# activity_monitor_v1_3.net
KiCad netlist of a schematic drawn in EAGLE
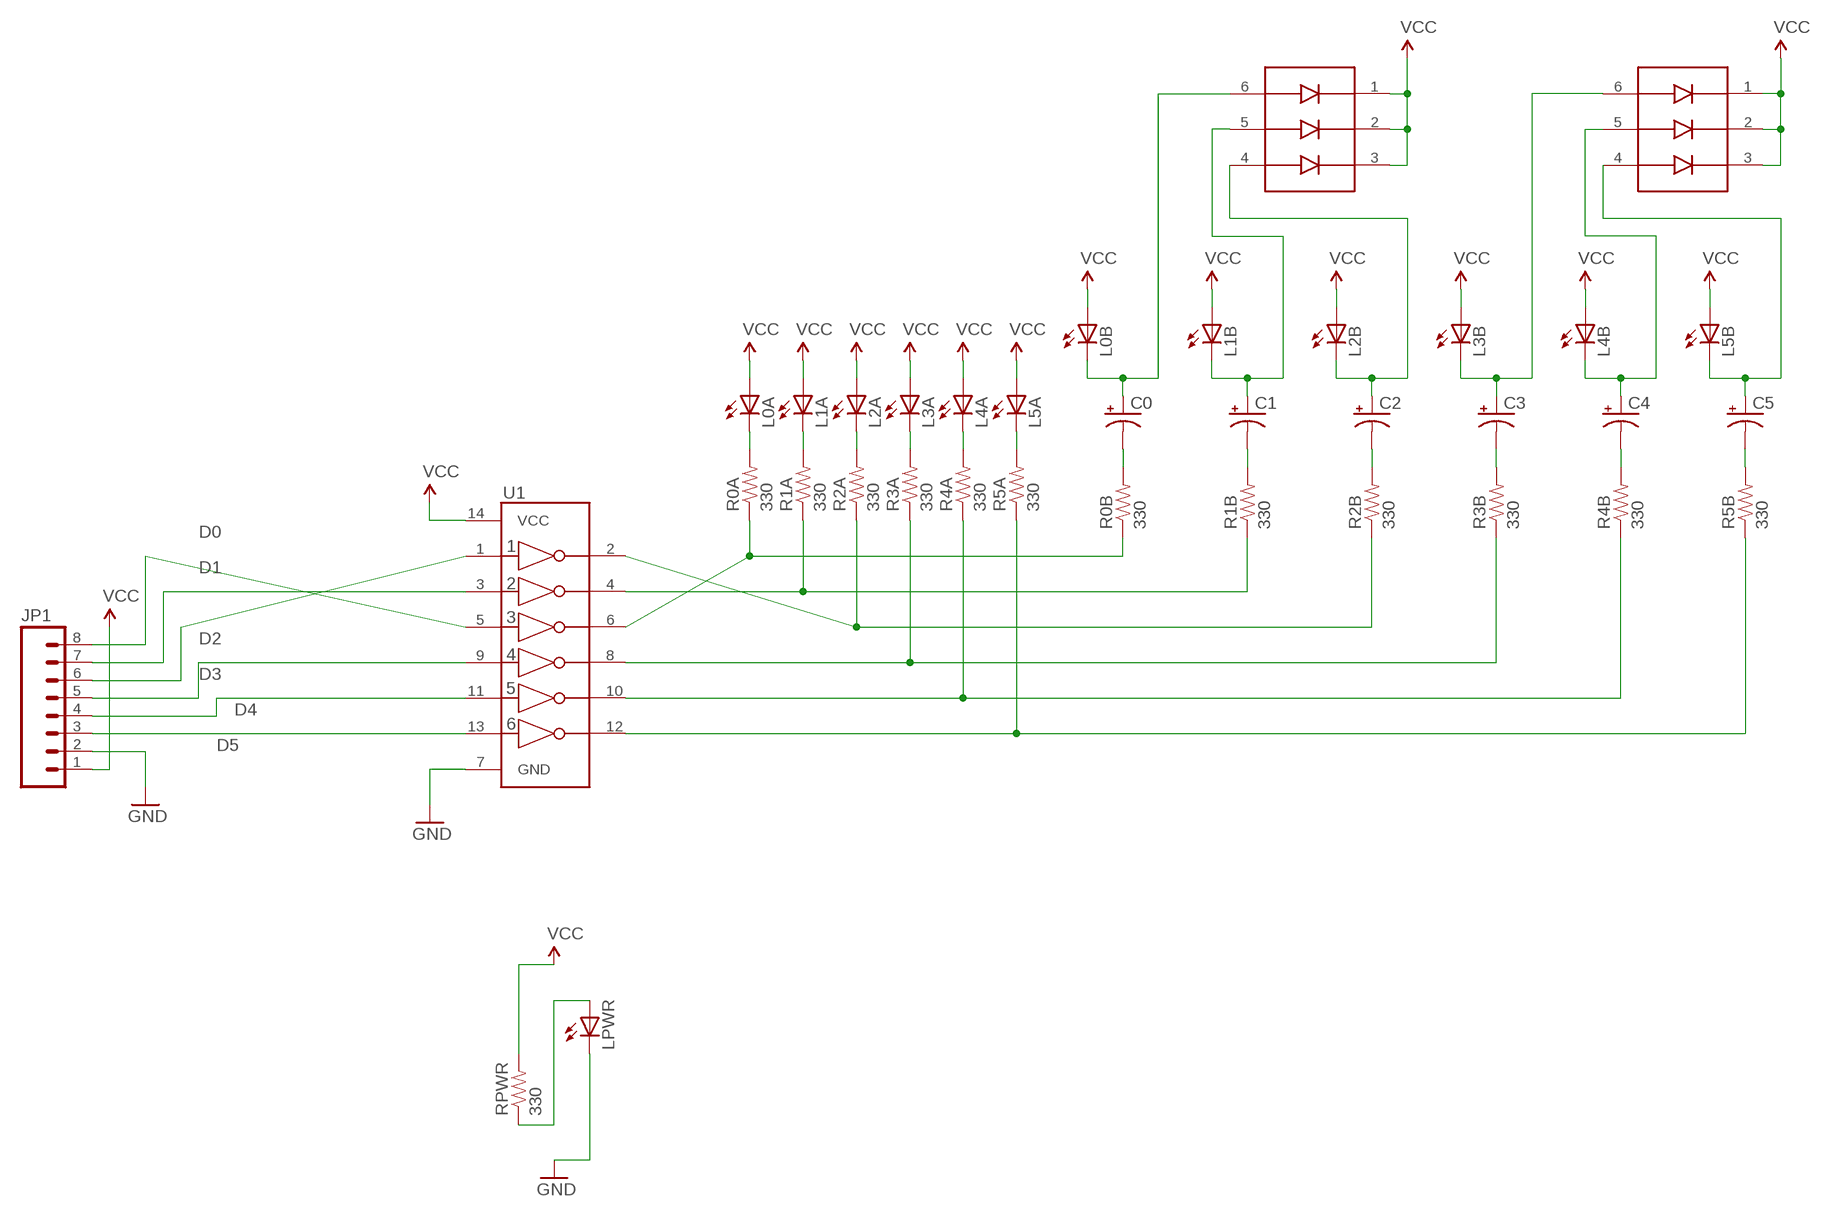
[diagram p0: schematic, sheet 1]

(export (version "E")
  (design (tool "Eeschema 10.0.6"))
  (components
    (comp (ref "C0")
      (value "10UF-TANT")
      (footprint "eagle-import:EIA3216")
      (libsource (lib "eagle-import") (part "10UF-TANT"))
    )
    (comp (ref "C1")
      (value "10UF-TANT")
      (footprint "eagle-import:EIA3216")
      (libsource (lib "eagle-import") (part "10UF-TANT"))
    )
    (comp (ref "C2")
      (value "10UF-TANT")
      (footprint "eagle-import:EIA3216")
      (libsource (lib "eagle-import") (part "10UF-TANT"))
    )
    (comp (ref "C3")
      (value "10UF-TANT")
      (footprint "eagle-import:EIA3216")
      (libsource (lib "eagle-import") (part "10UF-TANT"))
    )
    (comp (ref "C4")
      (value "10UF-TANT")
      (footprint "eagle-import:EIA3216")
      (libsource (lib "eagle-import") (part "10UF-TANT"))
    )
    (comp (ref "C5")
      (value "10UF-TANT")
      (footprint "eagle-import:EIA3216")
      (libsource (lib "eagle-import") (part "10UF-TANT"))
    )
    (comp (ref "JP1")
      (value "M081X08")
      (footprint "eagle-import:1X08")
      (libsource (lib "eagle-import") (part "M081X08"))
    )
    (comp (ref "L0A")
      (value "LED0603")
      (footprint "eagle-import:0603_LED")
      (libsource (lib "eagle-import") (part "LED0603"))
    )
    (comp (ref "L0B")
      (value "LED0603")
      (footprint "eagle-import:0603_LED")
      (libsource (lib "eagle-import") (part "LED0603"))
    )
    (comp (ref "L1A")
      (value "LED0603")
      (footprint "eagle-import:0603_LED")
      (libsource (lib "eagle-import") (part "LED0603"))
    )
    (comp (ref "L1B")
      (value "LED0603")
      (footprint "eagle-import:0603_LED")
      (libsource (lib "eagle-import") (part "LED0603"))
    )
    (comp (ref "L2A")
      (value "LED0603")
      (footprint "eagle-import:0603_LED")
      (libsource (lib "eagle-import") (part "LED0603"))
    )
    (comp (ref "L2B")
      (value "LED0603")
      (footprint "eagle-import:0603_LED")
      (libsource (lib "eagle-import") (part "LED0603"))
    )
    (comp (ref "L3A")
      (value "LED0603")
      (footprint "eagle-import:0603_LED")
      (libsource (lib "eagle-import") (part "LED0603"))
    )
    (comp (ref "L3B")
      (value "LED0603")
      (footprint "eagle-import:0603_LED")
      (libsource (lib "eagle-import") (part "LED0603"))
    )
    (comp (ref "L4A")
      (value "LED0603")
      (footprint "eagle-import:0603_LED")
      (libsource (lib "eagle-import") (part "LED0603"))
    )
    (comp (ref "L4B")
      (value "LED0603")
      (footprint "eagle-import:0603_LED")
      (libsource (lib "eagle-import") (part "LED0603"))
    )
    (comp (ref "L5A")
      (value "LED0603")
      (footprint "eagle-import:0603_LED")
      (libsource (lib "eagle-import") (part "LED0603"))
    )
    (comp (ref "L5B")
      (value "LED0603")
      (footprint "eagle-import:0603_LED")
      (libsource (lib "eagle-import") (part "LED0603"))
    )
    (comp (ref "LPWR")
      (value "LED0603")
      (footprint "eagle-import:0603_LED")
      (libsource (lib "eagle-import") (part "LED0603"))
    )
    (comp (ref "R0A")
      (value "330")
      (footprint "eagle-import:0603-RES")
      (libsource (lib "eagle-import") (part "RESISTOR0603"))
    )
    (comp (ref "R0B")
      (value "330")
      (footprint "eagle-import:0603-RES")
      (libsource (lib "eagle-import") (part "RESISTOR0603"))
    )
    (comp (ref "R1A")
      (value "330")
      (footprint "eagle-import:0603-RES")
      (libsource (lib "eagle-import") (part "RESISTOR0603"))
    )
    (comp (ref "R1B")
      (value "330")
      (footprint "eagle-import:0603-RES")
      (libsource (lib "eagle-import") (part "RESISTOR0603"))
    )
    (comp (ref "R2A")
      (value "330")
      (footprint "eagle-import:0603-RES")
      (libsource (lib "eagle-import") (part "RESISTOR0603"))
    )
    (comp (ref "R2B")
      (value "330")
      (footprint "eagle-import:0603-RES")
      (libsource (lib "eagle-import") (part "RESISTOR0603"))
    )
    (comp (ref "R3A")
      (value "330")
      (footprint "eagle-import:0603-RES")
      (libsource (lib "eagle-import") (part "RESISTOR0603"))
    )
    (comp (ref "R3B")
      (value "330")
      (footprint "eagle-import:0603-RES")
      (libsource (lib "eagle-import") (part "RESISTOR0603"))
    )
    (comp (ref "R4A")
      (value "330")
      (footprint "eagle-import:0603-RES")
      (libsource (lib "eagle-import") (part "RESISTOR0603"))
    )
    (comp (ref "R4B")
      (value "330")
      (footprint "eagle-import:0603-RES")
      (libsource (lib "eagle-import") (part "RESISTOR0603"))
    )
    (comp (ref "R5A")
      (value "330")
      (footprint "eagle-import:0603-RES")
      (libsource (lib "eagle-import") (part "RESISTOR0603"))
    )
    (comp (ref "R5B")
      (value "330")
      (footprint "eagle-import:0603-RES")
      (libsource (lib "eagle-import") (part "RESISTOR0603"))
    )
    (comp (ref "RPWR")
      (value "330")
      (footprint "eagle-import:0603-RES")
      (libsource (lib "eagle-import") (part "RESISTOR0603"))
    )
    (comp (ref "U$1")
      (value "SD103ATW-7-F")
      (footprint "eagle-import:SOT363")
      (libsource (lib "eagle-import") (part "SD103ATW-7-F"))
    )
    (comp (ref "U$2")
      (value "SD103ATW-7-F")
      (footprint "eagle-import:SOT363")
      (libsource (lib "eagle-import") (part "SD103ATW-7-F"))
    )
    (comp (ref "U1")
      (value "74HC04_HEX_INVERTERTSSOP14")
      (footprint "eagle-import:TSSOP14")
      (libsource (lib "eagle-import") (part "74HC04_HEX_INVERTERTSSOP14"))
    )
  )
  (nets
    (net (code "1") (name "/D0") (class "Default")
      (node (ref "JP1") (pin "8") (pinfunction "8_8") (pintype "passive"))
      (node (ref "U1") (pin "5") (pinfunction "3A_5") (pintype "input"))
    )
    (net (code "2") (name "/D1") (class "Default")
      (node (ref "JP1") (pin "7") (pinfunction "7_7") (pintype "passive"))
      (node (ref "U1") (pin "3") (pinfunction "2A_3") (pintype "input"))
    )
    (net (code "3") (name "/D2") (class "Default")
      (node (ref "JP1") (pin "6") (pinfunction "6_6") (pintype "passive"))
      (node (ref "U1") (pin "1") (pinfunction "1A_1") (pintype "input"))
    )
    (net (code "4") (name "/D3") (class "Default")
      (node (ref "JP1") (pin "5") (pinfunction "5_5") (pintype "passive"))
      (node (ref "U1") (pin "9") (pinfunction "4A_9") (pintype "input"))
    )
    (net (code "5") (name "/D4") (class "Default")
      (node (ref "JP1") (pin "4") (pinfunction "4_4") (pintype "passive"))
      (node (ref "U1") (pin "11") (pinfunction "5A_11") (pintype "input"))
    )
    (net (code "6") (name "/D5") (class "Default")
      (node (ref "JP1") (pin "3") (pinfunction "3_3") (pintype "passive"))
      (node (ref "U1") (pin "13") (pinfunction "6A_13") (pintype "input"))
    )
    (net (code "7") (name "GND") (class "Default")
      (node (ref "JP1") (pin "2") (pinfunction "2_2") (pintype "passive"))
      (node (ref "LPWR") (pin "C") (pinfunction "C_C") (pintype "passive"))
      (node (ref "U1") (pin "7") (pinfunction "GND_7") (pintype "power_in"))
    )
    (net (code "8") (name "Net-(C0-+)") (class "Default")
      (node (ref "C0") (pin "A") (pinfunction "+_A") (pintype "passive"))
      (node (ref "L0B") (pin "C") (pinfunction "C_C") (pintype "passive"))
      (node (ref "U$1") (pin "6") (pinfunction "I1_6") (pintype "bidirectional"))
    )
    (net (code "9") (name "Net-(C0--)") (class "Default")
      (node (ref "C0") (pin "C") (pinfunction "-_C") (pintype "passive"))
      (node (ref "R0B") (pin "2") (pinfunction "2_2") (pintype "passive"))
    )
    (net (code "10") (name "Net-(C1-+)") (class "Default")
      (node (ref "C1") (pin "A") (pinfunction "+_A") (pintype "passive"))
      (node (ref "L1B") (pin "C") (pinfunction "C_C") (pintype "passive"))
      (node (ref "U$1") (pin "5") (pinfunction "I2_5") (pintype "bidirectional"))
    )
    (net (code "11") (name "Net-(C1--)") (class "Default")
      (node (ref "C1") (pin "C") (pinfunction "-_C") (pintype "passive"))
      (node (ref "R1B") (pin "2") (pinfunction "2_2") (pintype "passive"))
    )
    (net (code "12") (name "Net-(C2-+)") (class "Default")
      (node (ref "C2") (pin "A") (pinfunction "+_A") (pintype "passive"))
      (node (ref "L2B") (pin "C") (pinfunction "C_C") (pintype "passive"))
      (node (ref "U$1") (pin "4") (pinfunction "I3_4") (pintype "bidirectional"))
    )
    (net (code "13") (name "Net-(C2--)") (class "Default")
      (node (ref "C2") (pin "C") (pinfunction "-_C") (pintype "passive"))
      (node (ref "R2B") (pin "2") (pinfunction "2_2") (pintype "passive"))
    )
    (net (code "14") (name "Net-(C3-+)") (class "Default")
      (node (ref "C3") (pin "A") (pinfunction "+_A") (pintype "passive"))
      (node (ref "L3B") (pin "C") (pinfunction "C_C") (pintype "passive"))
      (node (ref "U$2") (pin "6") (pinfunction "I1_6") (pintype "bidirectional"))
    )
    (net (code "15") (name "Net-(C3--)") (class "Default")
      (node (ref "C3") (pin "C") (pinfunction "-_C") (pintype "passive"))
      (node (ref "R3B") (pin "2") (pinfunction "2_2") (pintype "passive"))
    )
    (net (code "16") (name "Net-(C4-+)") (class "Default")
      (node (ref "C4") (pin "A") (pinfunction "+_A") (pintype "passive"))
      (node (ref "L4B") (pin "C") (pinfunction "C_C") (pintype "passive"))
      (node (ref "U$2") (pin "5") (pinfunction "I2_5") (pintype "bidirectional"))
    )
    (net (code "17") (name "Net-(C4--)") (class "Default")
      (node (ref "C4") (pin "C") (pinfunction "-_C") (pintype "passive"))
      (node (ref "R4B") (pin "2") (pinfunction "2_2") (pintype "passive"))
    )
    (net (code "18") (name "Net-(C5-+)") (class "Default")
      (node (ref "C5") (pin "A") (pinfunction "+_A") (pintype "passive"))
      (node (ref "L5B") (pin "C") (pinfunction "C_C") (pintype "passive"))
      (node (ref "U$2") (pin "4") (pinfunction "I3_4") (pintype "bidirectional"))
    )
    (net (code "19") (name "Net-(C5--)") (class "Default")
      (node (ref "C5") (pin "C") (pinfunction "-_C") (pintype "passive"))
      (node (ref "R5B") (pin "2") (pinfunction "2_2") (pintype "passive"))
    )
    (net (code "20") (name "Net-(L0A-PadC)") (class "Default")
      (node (ref "L0A") (pin "C") (pinfunction "C_C") (pintype "passive"))
      (node (ref "R0A") (pin "2") (pinfunction "2_2") (pintype "passive"))
    )
    (net (code "21") (name "Net-(L1A-PadC)") (class "Default")
      (node (ref "L1A") (pin "C") (pinfunction "C_C") (pintype "passive"))
      (node (ref "R1A") (pin "2") (pinfunction "2_2") (pintype "passive"))
    )
    (net (code "22") (name "Net-(L2A-PadC)") (class "Default")
      (node (ref "L2A") (pin "C") (pinfunction "C_C") (pintype "passive"))
      (node (ref "R2A") (pin "2") (pinfunction "2_2") (pintype "passive"))
    )
    (net (code "23") (name "Net-(L3A-PadC)") (class "Default")
      (node (ref "L3A") (pin "C") (pinfunction "C_C") (pintype "passive"))
      (node (ref "R3A") (pin "2") (pinfunction "2_2") (pintype "passive"))
    )
    (net (code "24") (name "Net-(L4A-PadC)") (class "Default")
      (node (ref "L4A") (pin "C") (pinfunction "C_C") (pintype "passive"))
      (node (ref "R4A") (pin "2") (pinfunction "2_2") (pintype "passive"))
    )
    (net (code "25") (name "Net-(L5A-PadC)") (class "Default")
      (node (ref "L5A") (pin "C") (pinfunction "C_C") (pintype "passive"))
      (node (ref "R5A") (pin "2") (pinfunction "2_2") (pintype "passive"))
    )
    (net (code "26") (name "Net-(LPWR-PadA)") (class "Default")
      (node (ref "LPWR") (pin "A") (pinfunction "A_A") (pintype "passive"))
      (node (ref "RPWR") (pin "1") (pinfunction "1_1") (pintype "passive"))
    )
    (net (code "27") (name "Net-(U1-1Y)") (class "Default")
      (node (ref "R2A") (pin "1") (pinfunction "1_1") (pintype "passive"))
      (node (ref "R2B") (pin "1") (pinfunction "1_1") (pintype "passive"))
      (node (ref "U1") (pin "2") (pinfunction "1Y_2") (pintype "output"))
    )
    (net (code "28") (name "Net-(U1-2Y)") (class "Default")
      (node (ref "R1A") (pin "1") (pinfunction "1_1") (pintype "passive"))
      (node (ref "R1B") (pin "1") (pinfunction "1_1") (pintype "passive"))
      (node (ref "U1") (pin "4") (pinfunction "2Y_4") (pintype "output"))
    )
    (net (code "29") (name "Net-(U1-3Y)") (class "Default")
      (node (ref "R0A") (pin "1") (pinfunction "1_1") (pintype "passive"))
      (node (ref "R0B") (pin "1") (pinfunction "1_1") (pintype "passive"))
      (node (ref "U1") (pin "6") (pinfunction "3Y_6") (pintype "output"))
    )
    (net (code "30") (name "Net-(U1-4Y)") (class "Default")
      (node (ref "R3A") (pin "1") (pinfunction "1_1") (pintype "passive"))
      (node (ref "R3B") (pin "1") (pinfunction "1_1") (pintype "passive"))
      (node (ref "U1") (pin "8") (pinfunction "4Y_8") (pintype "output"))
    )
    (net (code "31") (name "Net-(U1-5Y)") (class "Default")
      (node (ref "R4A") (pin "1") (pinfunction "1_1") (pintype "passive"))
      (node (ref "R4B") (pin "1") (pinfunction "1_1") (pintype "passive"))
      (node (ref "U1") (pin "10") (pinfunction "5Y_10") (pintype "output"))
    )
    (net (code "32") (name "Net-(U1-6Y)") (class "Default")
      (node (ref "R5A") (pin "1") (pinfunction "1_1") (pintype "passive"))
      (node (ref "R5B") (pin "1") (pinfunction "1_1") (pintype "passive"))
      (node (ref "U1") (pin "12") (pinfunction "6Y_12") (pintype "output"))
    )
    (net (code "33") (name "VCC") (class "Default")
      (node (ref "JP1") (pin "1") (pinfunction "1_1") (pintype "passive"))
      (node (ref "L0A") (pin "A") (pinfunction "A_A") (pintype "passive"))
      (node (ref "L0B") (pin "A") (pinfunction "A_A") (pintype "passive"))
      (node (ref "L1A") (pin "A") (pinfunction "A_A") (pintype "passive"))
      (node (ref "L1B") (pin "A") (pinfunction "A_A") (pintype "passive"))
      (node (ref "L2A") (pin "A") (pinfunction "A_A") (pintype "passive"))
      (node (ref "L2B") (pin "A") (pinfunction "A_A") (pintype "passive"))
      (node (ref "L3A") (pin "A") (pinfunction "A_A") (pintype "passive"))
      (node (ref "L3B") (pin "A") (pinfunction "A_A") (pintype "passive"))
      (node (ref "L4A") (pin "A") (pinfunction "A_A") (pintype "passive"))
      (node (ref "L4B") (pin "A") (pinfunction "A_A") (pintype "passive"))
      (node (ref "L5A") (pin "A") (pinfunction "A_A") (pintype "passive"))
      (node (ref "L5B") (pin "A") (pinfunction "A_A") (pintype "passive"))
      (node (ref "RPWR") (pin "2") (pinfunction "2_2") (pintype "passive"))
      (node (ref "U$1") (pin "1") (pinfunction "O1_1") (pintype "bidirectional"))
      (node (ref "U$1") (pin "2") (pinfunction "O2_2") (pintype "bidirectional"))
      (node (ref "U$1") (pin "3") (pinfunction "O3_3") (pintype "bidirectional"))
      (node (ref "U$2") (pin "1") (pinfunction "O1_1") (pintype "bidirectional"))
      (node (ref "U$2") (pin "2") (pinfunction "O2_2") (pintype "bidirectional"))
      (node (ref "U$2") (pin "3") (pinfunction "O3_3") (pintype "bidirectional"))
      (node (ref "U1") (pin "14") (pinfunction "VCC_14") (pintype "power_in"))
    )
  )
)
